# 2_AT_Link_ISO_MCU.net
KiCad netlist of a schematic drawn in Altium Designer
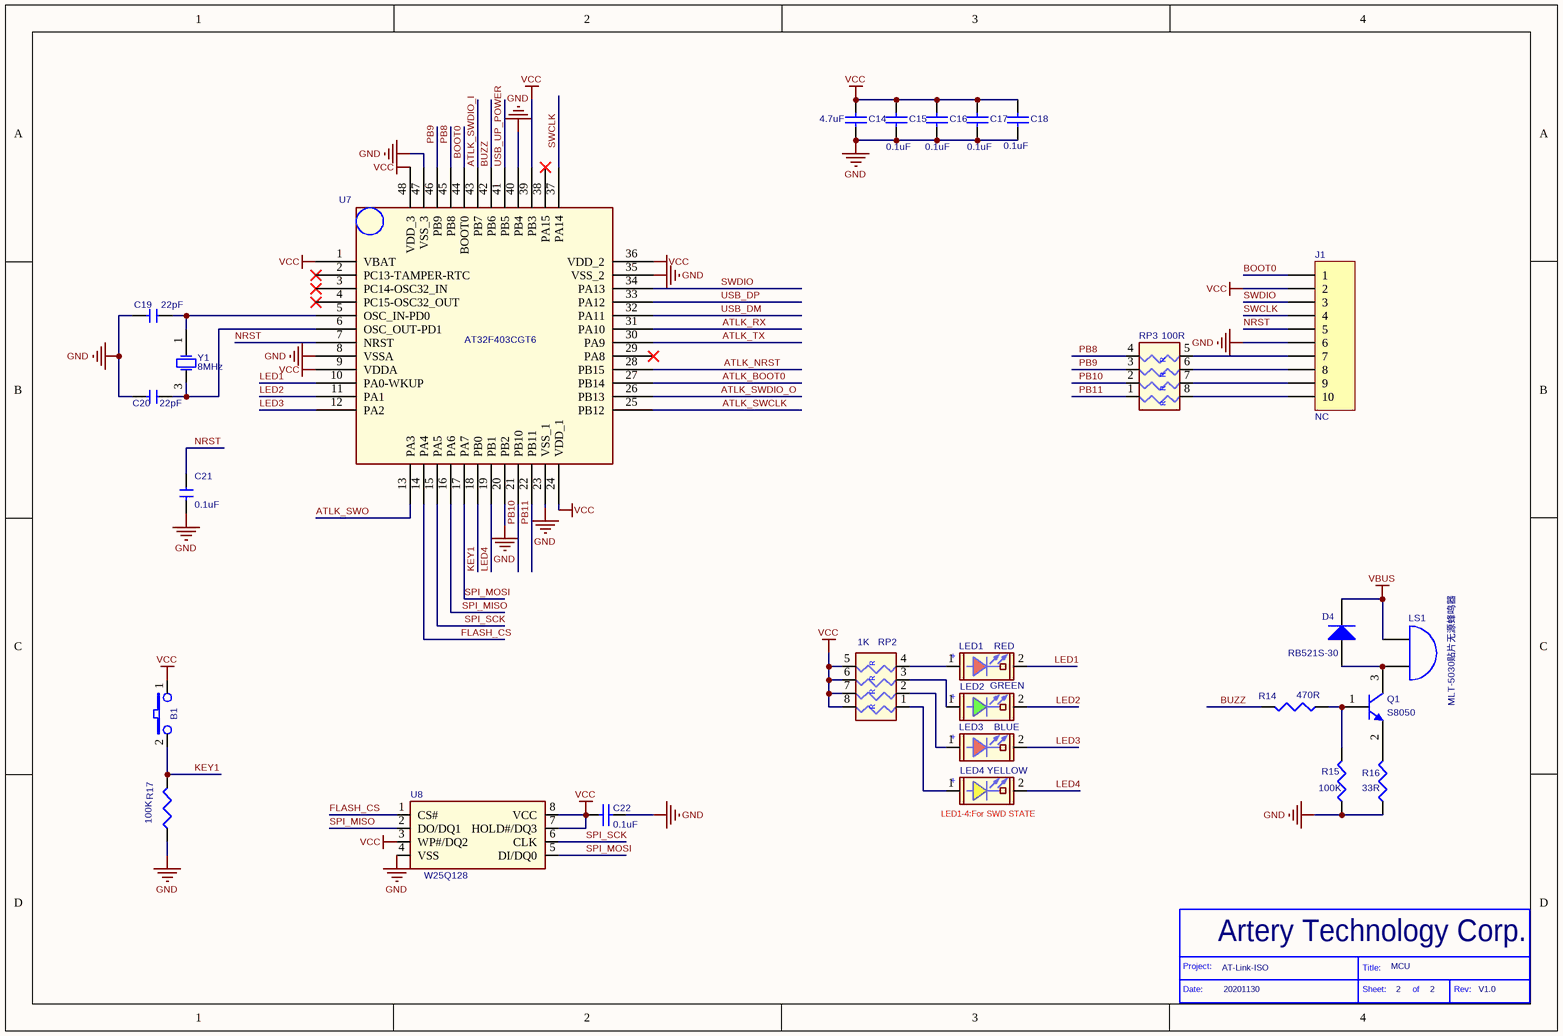
[diagram p0: 2_AT_Link_ISO_MCU.SchDoc]

(export (version "E")
  (design (tool "Eeschema 10.0.6"))
  (components
    (comp (ref "B1")
      (value "Button,SMD_2P")
      (description "两脚SMT贴片轻触开关3.5*6*5  黑色")
      (libsource (lib "*") (part "Push_Bottom,Blue,SMD_2P"))
    )
    (comp (ref "C14")
      (value "4.7uF")
      (description "贴片陶瓷电容4.7uF,16V,10%,X7R,SMD0603")
      (fields (field (name "PUBLISHER") "Altium Limited"))
      (libsource (lib "PcbLib") (part "Cap Semi"))
    )
    (comp (ref "C15")
      (value "0.1uF")
      (description "贴片陶瓷电容 0.1uF,16V,10%,X7R,SMD0603")
      (fields (field (name "PUBLISHER") "Altium Limited"))
      (libsource (lib "PcbLib") (part "Cap Semi"))
    )
    (comp (ref "C16")
      (value "0.1uF")
      (description "贴片陶瓷电容 0.1uF,16V,10%,X7R,SMD0603")
      (fields (field (name "PUBLISHER") "Altium Limited"))
      (libsource (lib "PcbLib") (part "Cap Semi"))
    )
    (comp (ref "C17")
      (value "0.1uF")
      (description "贴片陶瓷电容 0.1uF,16V,10%,X7R,SMD0603")
      (fields (field (name "PUBLISHER") "Altium Limited"))
      (libsource (lib "PcbLib") (part "Cap Semi"))
    )
    (comp (ref "C18")
      (value "0.1uF")
      (description "贴片陶瓷电容 0.1uF,16V,10%,X7R,SMD0603")
      (fields (field (name "PUBLISHER") "Altium Limited"))
      (libsource (lib "PcbLib") (part "Cap Semi"))
    )
    (comp (ref "C19")
      (value "22pF")
      (description "贴片陶瓷电容 22pF,50V,5%,COG,SMD0603")
      (libsource (lib "*") (part "10pF,50V,5%,SMD0603"))
    )
    (comp (ref "C20")
      (value "22pF")
      (description "贴片陶瓷电容 22pF,50V,5%,COG,SMD0603")
      (libsource (lib "*") (part "10pF,50V,5%,SMD0603"))
    )
    (comp (ref "C21")
      (value "0.1uF")
      (description "贴片陶瓷电容 0.1uF,16V,10%,X7R,SMD0603")
      (libsource (lib "*") (part "0.1uF,50V,20%,SMD0603"))
    )
    (comp (ref "C22")
      (value "0.1uF")
      (description "贴片陶瓷电容 0.1uF,16V,10%,X7R,SMD0603")
      (fields (field (name "PUBLISHER") "Altium Limited"))
      (libsource (lib "PcbLib") (part "Cap Semi"))
    )
    (comp (ref "D4")
      (value "RB521S-30")
      (footprint "SOD-523")
      (description "贴片二极管 RB521S-30 SOD-523")
      (fields (field (name "PUBLISHER") "Altium Limited"))
      (libsource (lib "Miscellaneous Devices") (part "Diode"))
    )
    (comp (ref "J1")
      (value "NC")
      (footprint "HDR1X10")
      (description "单排直插针2.54mm")
      (fields (field (name "PUBLISHER") "Altium Limited"))
      (libsource (lib "Miscellaneous Connectors") (part "Header 10"))
    )
    (comp (ref "LED1")
      (value "RED")
      (footprint "LED0603")
      (description "贴片LED  红色 0603")
      (libsource (lib "AT32F403_TINY_LQFP144_Library") (part "RED,SMD0603"))
    )
    (comp (ref "LED2")
      (value "GREEN")
      (footprint "LED0603")
      (description "贴片LED  绿色 0603")
      (libsource (lib "AT32F403_TINY_LQFP144_Library") (part "GREEN,SMD0603"))
    )
    (comp (ref "LED3")
      (value "BLUE")
      (footprint "LED0603")
      (description "贴片LED  蓝色 0603")
      (libsource (lib "AT32F403_TINY_LQFP144_Library") (part "RED,SMD0603"))
    )
    (comp (ref "LED4")
      (value "YELLOW")
      (footprint "LED0603")
      (description "贴片LED  黄色 0603")
      (libsource (lib "Schlib1") (part "YELLOW,SMD0603"))
    )
    (comp (ref "LS1")
      (value "MLT-5030贴片无源蜂鸣器")
      (footprint "BUZZER - 5030")
      (fields (field (name "PUBLISHER") "Altium Limited"))
      (libsource (lib "Miscellaneous Devices") (part "Bell"))
    )
    (comp (ref "Q1")
      (value "S8050")
      (footprint "SOT-23")
      (description "三极管SS8050 SOT-23")
      (libsource (lib "Schlib") (part "NPN"))
    )
    (comp (ref "R14")
      (value "470R")
      (description "贴片电阻 470R 5% 1/10W 0603")
      (libsource (lib "*") (part "470,1/10W,1%,SMD0603"))
    )
    (comp (ref "R15")
      (value "100K")
      (description "贴片电阻 100K 5% 1/10W 0603")
      (libsource (lib "*") (part "470,1/10W,1%,SMD0603"))
    )
    (comp (ref "R16")
      (value "33R")
      (description "贴片电阻 33R 5% 1/10W 0603")
      (libsource (lib "*") (part "470,1/10W,1%,SMD0603"))
    )
    (comp (ref "R17")
      (value "100K")
      (description "贴片电阻 100K 5% 1/10W 0603")
      (libsource (lib "*") (part "10K,1/10W,1%,SMD0603"))
    )
    (comp (ref "RP2")
      (value "1K")
      (description "贴片排阻 1K 5% 1/16W 0603")
      (libsource (lib "") (part "22,1/16W,5%,8P4R_1"))
    )
    (comp (ref "RP3")
      (value "100R")
      (description "贴片排阻 100R 5% 1/16W 0603")
      (libsource (lib "*") (part "22,1/16W,5%,8P4R"))
    )
    (comp (ref "U7")
      (value "AT32F403CGT6")
      (footprint "AT403-ALL-PcbLib:LQFP48 - 2")
      (libsource (lib "AT403-ALL-Package") (part "LQFP48&QFN48"))
    )
    (comp (ref "U8")
      (value "W25Q128")
      (footprint "SOIC-8_208mil")
      (description "W25Q128JVSIQTR")
      (libsource (lib "AT32F403_TINY_LQFP144_Library") (part "W25Q128FVSIQ,SOIC8_1"))
    )
    (comp (ref "Y1")
      (value "8MHz")
      (footprint "XTAL_5032")
      (description "无源晶振8MHz TZ0211E 5032_4,20pF,20PPM")
      (libsource (lib "Artery_Wanbing") (part "SMD-5032_4P  8MHZ 20PF 10PPM"))
    )
  )
  (nets
    (net (code "1") (name "/ATLK_BOOT0") (class "Default")
      (node (ref "U7") (pin "27") (pinfunction "PB14_27") (pintype "passive"))
    )
    (net (code "2") (name "/ATLK_NRST") (class "Default")
      (node (ref "U7") (pin "28") (pinfunction "PB15_28") (pintype "passive"))
    )
    (net (code "3") (name "/ATLK_RX") (class "Default")
      (node (ref "U7") (pin "31") (pinfunction "PA10_31") (pintype "passive"))
    )
    (net (code "4") (name "/ATLK_SWCLK") (class "Default")
      (node (ref "U7") (pin "25") (pinfunction "PB12_25") (pintype "passive"))
    )
    (net (code "5") (name "/ATLK_SWDIO_I") (class "Default")
      (node (ref "U7") (pin "43") (pinfunction "PB7_43") (pintype "passive"))
    )
    (net (code "6") (name "/ATLK_SWDIO_O") (class "Default")
      (node (ref "U7") (pin "26") (pinfunction "PB13_26") (pintype "passive"))
    )
    (net (code "7") (name "/ATLK_SWO") (class "Default")
      (node (ref "U7") (pin "13") (pinfunction "PA3_13") (pintype "passive"))
    )
    (net (code "8") (name "/ATLK_TX") (class "Default")
      (node (ref "U7") (pin "30") (pinfunction "PA9_30") (pintype "passive"))
    )
    (net (code "9") (name "/BOOT0") (class "Default")
      (node (ref "J1") (pin "1") (pinfunction "1_1") (pintype "passive"))
      (node (ref "U7") (pin "44") (pinfunction "BOOT0_44") (pintype "passive"))
    )
    (net (code "10") (name "/BUZZ") (class "Default")
      (node (ref "R14") (pin "2") (pinfunction "2_2") (pintype "passive"))
      (node (ref "U7") (pin "42") (pinfunction "PB6_42") (pintype "passive"))
    )
    (net (code "11") (name "/FLASH_CS") (class "Default")
      (node (ref "U7") (pin "14") (pinfunction "PA4_14") (pintype "passive"))
      (node (ref "U8") (pin "1") (pinfunction "CS#_1") (pintype "passive"))
    )
    (net (code "12") (name "/KEY1") (class "Default")
      (node (ref "B1") (pin "2") (pinfunction "2_2") (pintype "passive"))
      (node (ref "R17") (pin "2") (pinfunction "2_2") (pintype "passive"))
      (node (ref "U7") (pin "18") (pinfunction "PB0_18") (pintype "passive"))
    )
    (net (code "13") (name "/LED1") (class "Default")
      (node (ref "LED1") (pin "2") (pinfunction "CATHODE_2") (pintype "passive"))
      (node (ref "U7") (pin "10") (pinfunction "PA0-WKUP_10") (pintype "passive"))
    )
    (net (code "14") (name "/LED2") (class "Default")
      (node (ref "LED2") (pin "2") (pinfunction "CATHODE_2") (pintype "passive"))
      (node (ref "U7") (pin "11") (pinfunction "PA1_11") (pintype "passive"))
    )
    (net (code "15") (name "/LED3") (class "Default")
      (node (ref "LED3") (pin "2") (pinfunction "CATHODE_2") (pintype "passive"))
      (node (ref "U7") (pin "12") (pinfunction "PA2_12") (pintype "passive"))
    )
    (net (code "16") (name "/LED4") (class "Default")
      (node (ref "LED4") (pin "2") (pinfunction "CATHODE_2") (pintype "passive"))
      (node (ref "U7") (pin "19") (pinfunction "PB1_19") (pintype "passive"))
    )
    (net (code "17") (name "/NRST") (class "Default")
      (node (ref "C21") (pin "1") (pinfunction "1_1") (pintype "passive"))
      (node (ref "J1") (pin "5") (pinfunction "5_5") (pintype "passive"))
      (node (ref "U7") (pin "7") (pinfunction "NRST_7") (pintype "passive"))
    )
    (net (code "18") (name "/PB8") (class "Default")
      (node (ref "RP3") (pin "4") (pinfunction "4_4") (pintype "passive"))
      (node (ref "U7") (pin "45") (pinfunction "PB8_45") (pintype "passive"))
    )
    (net (code "19") (name "/PB9") (class "Default")
      (node (ref "RP3") (pin "3") (pinfunction "3_3") (pintype "passive"))
      (node (ref "U7") (pin "46") (pinfunction "PB9_46") (pintype "passive"))
    )
    (net (code "20") (name "/PB10") (class "Default")
      (node (ref "RP3") (pin "2") (pinfunction "2_2") (pintype "passive"))
      (node (ref "U7") (pin "21") (pinfunction "PB10_21") (pintype "passive"))
    )
    (net (code "21") (name "/PB11") (class "Default")
      (node (ref "RP3") (pin "1") (pinfunction "1_1") (pintype "passive"))
      (node (ref "U7") (pin "22") (pinfunction "PB11_22") (pintype "passive"))
    )
    (net (code "22") (name "/SPI_MISO") (class "Default")
      (node (ref "U7") (pin "16") (pinfunction "PA6_16") (pintype "passive"))
      (node (ref "U8") (pin "2") (pinfunction "DO/DQ1_2") (pintype "passive"))
    )
    (net (code "23") (name "/SPI_MOSI") (class "Default")
      (node (ref "U7") (pin "17") (pinfunction "PA7_17") (pintype "passive"))
      (node (ref "U8") (pin "5") (pinfunction "DI/DQ0_5") (pintype "passive"))
    )
    (net (code "24") (name "/SPI_SCK") (class "Default")
      (node (ref "U7") (pin "15") (pinfunction "PA5_15") (pintype "passive"))
      (node (ref "U8") (pin "6") (pinfunction "CLK_6") (pintype "passive"))
    )
    (net (code "25") (name "/SWCLK") (class "Default")
      (node (ref "J1") (pin "4") (pinfunction "4_4") (pintype "passive"))
      (node (ref "U7") (pin "37") (pinfunction "PA14_37") (pintype "passive"))
    )
    (net (code "26") (name "/SWDIO") (class "Default")
      (node (ref "J1") (pin "3") (pinfunction "3_3") (pintype "passive"))
      (node (ref "U7") (pin "34") (pinfunction "PA13_34") (pintype "passive"))
    )
    (net (code "27") (name "/USB_DM") (class "Default")
      (node (ref "U7") (pin "32") (pinfunction "PA11_32") (pintype "passive"))
    )
    (net (code "28") (name "/USB_DP") (class "Default")
      (node (ref "U7") (pin "33") (pinfunction "PA12_33") (pintype "passive"))
    )
    (net (code "29") (name "/USB_UP_POWER") (class "Default")
      (node (ref "U7") (pin "41") (pinfunction "PB5_41") (pintype "passive"))
    )
    (net (code "30") (name "GND") (class "Default")
      (node (ref "C14") (pin "1") (pinfunction "1_1") (pintype "passive"))
      (node (ref "C15") (pin "1") (pinfunction "1_1") (pintype "passive"))
      (node (ref "C16") (pin "1") (pinfunction "1_1") (pintype "passive"))
      (node (ref "C17") (pin "1") (pinfunction "1_1") (pintype "passive"))
      (node (ref "C18") (pin "1") (pinfunction "1_1") (pintype "passive"))
      (node (ref "C19") (pin "2") (pinfunction "2_2") (pintype "passive"))
      (node (ref "C20") (pin "2") (pinfunction "2_2") (pintype "passive"))
      (node (ref "C21") (pin "2") (pinfunction "2_2") (pintype "passive"))
      (node (ref "C22") (pin "1") (pinfunction "1_1") (pintype "passive"))
      (node (ref "J1") (pin "6") (pinfunction "6_6") (pintype "passive"))
      (node (ref "R15") (pin "1") (pinfunction "1_1") (pintype "passive"))
      (node (ref "R16") (pin "1") (pinfunction "1_1") (pintype "passive"))
      (node (ref "R17") (pin "1") (pinfunction "1_1") (pintype "passive"))
      (node (ref "U7") (pin "20") (pinfunction "PB2_20") (pintype "passive"))
      (node (ref "U7") (pin "23") (pinfunction "VSS_1_23") (pintype "passive"))
      (node (ref "U7") (pin "35") (pinfunction "VSS_2_35") (pintype "passive"))
      (node (ref "U7") (pin "40") (pinfunction "PB4_40") (pintype "passive"))
      (node (ref "U7") (pin "47") (pinfunction "VSS_3_47") (pintype "passive"))
      (node (ref "U7") (pin "8") (pinfunction "VSSA_8") (pintype "passive"))
      (node (ref "U8") (pin "4") (pinfunction "VSS_4") (pintype "power_in"))
    )
    (net (code "31") (name "Net-(D4-A)") (class "Default")
      (node (ref "D4") (pin "1") (pinfunction "A_1") (pintype "passive"))
      (node (ref "LS1") (pin "2") (pinfunction "B_2") (pintype "passive"))
      (node (ref "Q1") (pin "3") (pinfunction "C_3") (pintype "passive"))
    )
    (net (code "32") (name "Net-(J1-Pad7)") (class "Default")
      (node (ref "J1") (pin "7") (pinfunction "7_7") (pintype "passive"))
      (node (ref "RP3") (pin "5") (pinfunction "5_5") (pintype "passive"))
    )
    (net (code "33") (name "Net-(J1-Pad8)") (class "Default")
      (node (ref "J1") (pin "8") (pinfunction "8_8") (pintype "passive"))
      (node (ref "RP3") (pin "6") (pinfunction "6_6") (pintype "passive"))
    )
    (net (code "34") (name "Net-(J1-Pad9)") (class "Default")
      (node (ref "J1") (pin "9") (pinfunction "9_9") (pintype "passive"))
      (node (ref "RP3") (pin "7") (pinfunction "7_7") (pintype "passive"))
    )
    (net (code "35") (name "Net-(J1-Pad10)") (class "Default")
      (node (ref "J1") (pin "10") (pinfunction "10_10") (pintype "passive"))
      (node (ref "RP3") (pin "8") (pinfunction "8_8") (pintype "passive"))
    )
    (net (code "36") (name "Net-(LED1-ANODE)") (class "Default")
      (node (ref "LED1") (pin "1") (pinfunction "ANODE_1") (pintype "passive"))
      (node (ref "RP2") (pin "4") (pinfunction "4_4") (pintype "passive"))
    )
    (net (code "37") (name "Net-(LED2-ANODE)") (class "Default")
      (node (ref "LED2") (pin "1") (pinfunction "ANODE_1") (pintype "passive"))
      (node (ref "RP2") (pin "3") (pinfunction "3_3") (pintype "passive"))
    )
    (net (code "38") (name "Net-(LED3-ANODE)") (class "Default")
      (node (ref "LED3") (pin "1") (pinfunction "ANODE_1") (pintype "passive"))
      (node (ref "RP2") (pin "2") (pinfunction "2_2") (pintype "passive"))
    )
    (net (code "39") (name "Net-(LED4-ANODE)") (class "Default")
      (node (ref "LED4") (pin "1") (pinfunction "ANODE_1") (pintype "passive"))
      (node (ref "RP2") (pin "1") (pinfunction "1_1") (pintype "passive"))
    )
    (net (code "40") (name "Net-(Q1-B)") (class "Default")
      (node (ref "Q1") (pin "1") (pinfunction "B_1") (pintype "passive"))
      (node (ref "R14") (pin "1") (pinfunction "1_1") (pintype "passive"))
      (node (ref "R15") (pin "2") (pinfunction "2_2") (pintype "passive"))
    )
    (net (code "41") (name "Net-(Q1-E)") (class "Default")
      (node (ref "Q1") (pin "2") (pinfunction "E_2") (pintype "passive"))
      (node (ref "R16") (pin "2") (pinfunction "2_2") (pintype "passive"))
    )
    (net (code "42") (name "Net-(U7-OSC_IN-PD0)") (class "Default")
      (node (ref "C19") (pin "1") (pinfunction "1_1") (pintype "passive"))
      (node (ref "U7") (pin "5") (pinfunction "OSC_IN-PD0_5") (pintype "passive"))
      (node (ref "Y1") (pin "1") (pinfunction "OSC1_1") (pintype "passive"))
    )
    (net (code "43") (name "Net-(U7-OSC_OUT-PD1)") (class "Default")
      (node (ref "C20") (pin "1") (pinfunction "1_1") (pintype "passive"))
      (node (ref "U7") (pin "6") (pinfunction "OSC_OUT-PD1_6") (pintype "passive"))
      (node (ref "Y1") (pin "3") (pinfunction "OSC2_3") (pintype "passive"))
    )
    (net (code "44") (name "VBUS") (class "Default")
      (node (ref "D4") (pin "2") (pinfunction "K_2") (pintype "passive"))
      (node (ref "LS1") (pin "1") (pinfunction "A_1") (pintype "passive"))
    )
    (net (code "45") (name "VCC") (class "Default")
      (node (ref "B1") (pin "1") (pinfunction "1_1") (pintype "passive"))
      (node (ref "C14") (pin "2") (pinfunction "2_2") (pintype "passive"))
      (node (ref "C15") (pin "2") (pinfunction "2_2") (pintype "passive"))
      (node (ref "C16") (pin "2") (pinfunction "2_2") (pintype "passive"))
      (node (ref "C17") (pin "2") (pinfunction "2_2") (pintype "passive"))
      (node (ref "C18") (pin "2") (pinfunction "2_2") (pintype "passive"))
      (node (ref "C22") (pin "2") (pinfunction "2_2") (pintype "passive"))
      (node (ref "J1") (pin "2") (pinfunction "2_2") (pintype "passive"))
      (node (ref "RP2") (pin "5") (pinfunction "5_5") (pintype "passive"))
      (node (ref "RP2") (pin "6") (pinfunction "6_6") (pintype "passive"))
      (node (ref "RP2") (pin "7") (pinfunction "7_7") (pintype "passive"))
      (node (ref "RP2") (pin "8") (pinfunction "8_8") (pintype "passive"))
      (node (ref "U7") (pin "1") (pinfunction "VBAT_1") (pintype "passive"))
      (node (ref "U7") (pin "24") (pinfunction "VDD_1_24") (pintype "passive"))
      (node (ref "U7") (pin "36") (pinfunction "VDD_2_36") (pintype "passive"))
      (node (ref "U7") (pin "39") (pinfunction "PB3_39") (pintype "passive"))
      (node (ref "U7") (pin "48") (pinfunction "VDD_3_48") (pintype "passive"))
      (node (ref "U7") (pin "9") (pinfunction "VDDA_9") (pintype "passive"))
      (node (ref "U8") (pin "3") (pinfunction "WP#/DQ2_3") (pintype "passive"))
      (node (ref "U8") (pin "7") (pinfunction "HOLD#/DQ3_7") (pintype "passive"))
      (node (ref "U8") (pin "8") (pinfunction "VCC_8") (pintype "power_in"))
    )
    (net (code "46") (name "unconnected-(U7-PA8-Pad29)") (class "Default")
      (node (ref "U7") (pin "29") (pinfunction "PA8_29") (pintype "passive+no_connect"))
    )
    (net (code "47") (name "unconnected-(U7-PA15-Pad38)") (class "Default")
      (node (ref "U7") (pin "38") (pinfunction "PA15_38") (pintype "passive+no_connect"))
    )
    (net (code "48") (name "unconnected-(U7-PC13-TAMPER-RTC-Pad2)") (class "Default")
      (node (ref "U7") (pin "2") (pinfunction "PC13-TAMPER-RTC_2") (pintype "passive+no_connect"))
    )
    (net (code "49") (name "unconnected-(U7-PC14-OSC32_IN-Pad3)") (class "Default")
      (node (ref "U7") (pin "3") (pinfunction "PC14-OSC32_IN_3") (pintype "passive+no_connect"))
    )
    (net (code "50") (name "unconnected-(U7-PC15-OSC32_OUT-Pad4)") (class "Default")
      (node (ref "U7") (pin "4") (pinfunction "PC15-OSC32_OUT_4") (pintype "passive+no_connect"))
    )
  )
)
